# SENSORS_FMU_REV_2A.net
KiCad netlist of a schematic drawn in Altium Designer
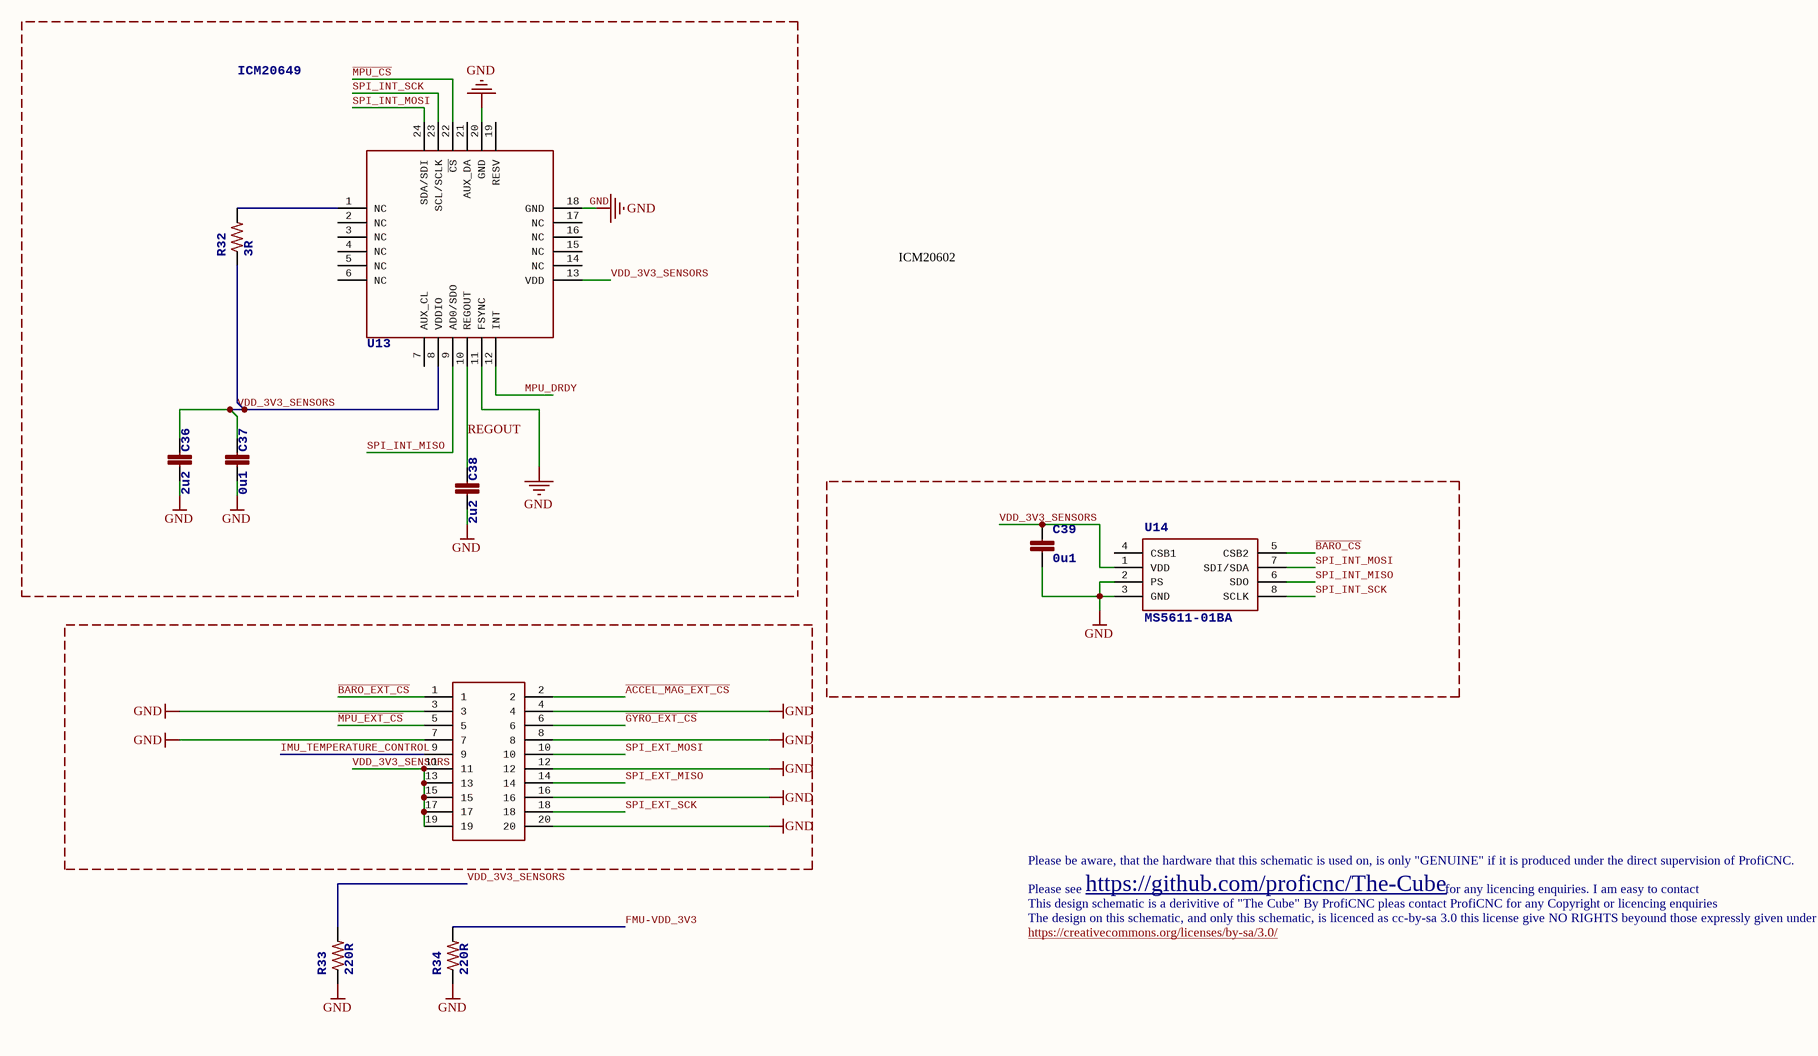
[diagram p0: SENSORS_FMU_REV_2A.SchDoc]

(export (version "E")
  (design (tool "Eeschema 10.0.6"))
  (components
    (comp (ref "C36")
      (value "2u2")
      (footprint "0603-CAP")
      (description "CAP CER 2.2UF 16V 10% X6S 0603")
      (libsource (lib "pixhawk2") (part "CAP0603"))
    )
    (comp (ref "C37")
      (value "0u1")
      (footprint "0402-CAP")
      (description "CAP CER 0.1UF 16V Y5V 0402")
      (libsource (lib "pixhawk2") (part "CAP0402"))
    )
    (comp (ref "C38")
      (value "2u2")
      (footprint "0603-CAP")
      (description "CAP CER 2.2UF 16V 10% X6S 0603")
      (libsource (lib "pixhawk2") (part "CAP0603"))
    )
    (comp (ref "C39")
      (value "0u1")
      (footprint "0402-CAP")
      (description "CAP CER 0.1UF 16V Y5V 0402")
      (libsource (lib "pixhawk2") (part "CAP0402"))
    )
    (comp (ref "R32")
      (value "3R")
      (footprint "0201-RES")
      (description "RES 3OHM 1/16W 1% 0201 SMD")
      (libsource (lib "altium-import") (part "root_1_RESISTOR0402-RES_"))
    )
    (comp (ref "R33")
      (value "220R")
      (footprint "0402-RES")
      (description "RES 220 OHM 1/16W 1% 0402 SMD")
      (libsource (lib "pixhawk2") (part "RESISTOR0402-RES"))
    )
    (comp (ref "R34")
      (value "220R")
      (footprint "0402-RES")
      (description "RES 220 OHM 1/16W 1% 0402 SMD")
      (libsource (lib "pixhawk2") (part "RESISTOR0402-RES"))
    )
    (comp (ref "U$2")
      (value "DF40C-20-DS")
      (footprint "DF-40C-20DS")
      (description "CONN RCPT 20POS 0.4MM SMD GOLD")
      (libsource (lib "pixhawk2") (part "DF40C-20-DS"))
    )
    (comp (ref "U13")
      (value "ICM20649")
      (footprint "ICM20649")
      (libsource (lib "IMU_REV_2A") (part "ICM20649"))
    )
    (comp (ref "U14")
      (value "MS5611-01BA")
      (footprint "MS5611-01BA")
      (description "Board Mount Pressure Sensors")
      (libsource (lib "pixhawk2") (part "MS5611-01BA"))
    )
  )
  (nets
    (net (code "1") (name "/FMU-VDD_3V3") (class "Default")
      (node (ref "R34") (pin "P$2") (pinfunction "2_P$2") (pintype "passive"))
    )
    (net (code "2") (name "/IMU_TEMPERATURE_CONTROL") (class "Default")
      (node (ref "U$2") (pin "9") (pinfunction "9_9") (pintype "passive"))
    )
    (net (code "3") (name "/MPU_DRDY") (class "Default")
      (node (ref "U13") (pin "12") (pinfunction "INT_12") (pintype "passive"))
    )
    (net (code "4") (name "/REGOUT") (class "Default")
      (node (ref "C38") (pin "P$1") (pinfunction "1_P$1") (pintype "passive"))
      (node (ref "U13") (pin "10") (pinfunction "REGOUT_10") (pintype "passive"))
    )
    (net (code "5") (name "/SPI_EXT_MISO") (class "Default")
      (node (ref "U$2") (pin "14") (pinfunction "14_14") (pintype "passive"))
    )
    (net (code "6") (name "/SPI_EXT_MOSI") (class "Default")
      (node (ref "U$2") (pin "10") (pinfunction "10_10") (pintype "passive"))
    )
    (net (code "7") (name "/SPI_EXT_SCK") (class "Default")
      (node (ref "U$2") (pin "18") (pinfunction "18_18") (pintype "passive"))
    )
    (net (code "8") (name "/SPI_INT_MISO") (class "Default")
      (node (ref "U13") (pin "9") (pinfunction "AD0/SDO_9") (pintype "passive"))
      (node (ref "U14") (pin "6") (pinfunction "SDO_6") (pintype "passive"))
    )
    (net (code "9") (name "/SPI_INT_MOSI") (class "Default")
      (node (ref "U13") (pin "24") (pinfunction "SDA/SDI_24") (pintype "passive"))
      (node (ref "U14") (pin "7") (pinfunction "SDI/SDA_7") (pintype "passive"))
    )
    (net (code "10") (name "/SPI_INT_SCK") (class "Default")
      (node (ref "U13") (pin "23") (pinfunction "SCL/SCLK_23") (pintype "passive"))
      (node (ref "U14") (pin "8") (pinfunction "SCLK_8") (pintype "passive"))
    )
    (net (code "11") (name "/VDD_3V3_SENSORS") (class "Default")
      (node (ref "C36") (pin "P$1") (pinfunction "1_P$1") (pintype "passive"))
      (node (ref "C37") (pin "P$1") (pinfunction "1_P$1") (pintype "passive"))
      (node (ref "C39") (pin "P$1") (pinfunction "1_P$1") (pintype "passive"))
      (node (ref "R32") (pin "1") (pinfunction "1_1") (pintype "passive"))
      (node (ref "R33") (pin "P$2") (pinfunction "2_P$2") (pintype "passive"))
      (node (ref "U$2") (pin "11") (pinfunction "11_11") (pintype "passive"))
      (node (ref "U$2") (pin "13") (pinfunction "13_13") (pintype "passive"))
      (node (ref "U$2") (pin "15") (pinfunction "15_15") (pintype "passive"))
      (node (ref "U$2") (pin "17") (pinfunction "17_17") (pintype "passive"))
      (node (ref "U$2") (pin "19") (pinfunction "19_19") (pintype "passive"))
      (node (ref "U13") (pin "13") (pinfunction "VDD_13") (pintype "passive"))
      (node (ref "U13") (pin "8") (pinfunction "VDDIO_8") (pintype "passive"))
      (node (ref "U14") (pin "1") (pinfunction "VDD_1") (pintype "passive"))
    )
    (net (code "12") (name "/~{ACCEL_MAG_EXT_CS}") (class "Default")
      (node (ref "U$2") (pin "2") (pinfunction "2_2") (pintype "passive"))
    )
    (net (code "13") (name "/~{BARO_CS}") (class "Default")
      (node (ref "U14") (pin "5") (pinfunction "CSB2_5") (pintype "passive"))
    )
    (net (code "14") (name "/~{BARO_EXT_CS}") (class "Default")
      (node (ref "U$2") (pin "1") (pinfunction "1_1") (pintype "passive"))
    )
    (net (code "15") (name "/~{GYRO_EXT_CS}") (class "Default")
      (node (ref "U$2") (pin "6") (pinfunction "6_6") (pintype "passive"))
    )
    (net (code "16") (name "/~{MPU_CS}") (class "Default")
      (node (ref "U13") (pin "22") (pinfunction "~{CS}_22") (pintype "passive"))
    )
    (net (code "17") (name "/~{MPU_EXT_CS}") (class "Default")
      (node (ref "U$2") (pin "5") (pinfunction "5_5") (pintype "passive"))
    )
    (net (code "18") (name "GND") (class "Default")
      (node (ref "C36") (pin "P$2") (pinfunction "2_P$2") (pintype "passive"))
      (node (ref "C37") (pin "P$2") (pinfunction "2_P$2") (pintype "passive"))
      (node (ref "C38") (pin "P$2") (pinfunction "2_P$2") (pintype "passive"))
      (node (ref "C39") (pin "P$2") (pinfunction "2_P$2") (pintype "passive"))
      (node (ref "R33") (pin "P$1") (pinfunction "1_P$1") (pintype "passive"))
      (node (ref "R34") (pin "P$1") (pinfunction "1_P$1") (pintype "passive"))
      (node (ref "U$2") (pin "12") (pinfunction "12_12") (pintype "passive"))
      (node (ref "U$2") (pin "16") (pinfunction "16_16") (pintype "passive"))
      (node (ref "U$2") (pin "20") (pinfunction "20_20") (pintype "passive"))
      (node (ref "U$2") (pin "3") (pinfunction "3_3") (pintype "passive"))
      (node (ref "U$2") (pin "4") (pinfunction "4_4") (pintype "passive"))
      (node (ref "U$2") (pin "7") (pinfunction "7_7") (pintype "passive"))
      (node (ref "U$2") (pin "8") (pinfunction "8_8") (pintype "passive"))
      (node (ref "U13") (pin "11") (pinfunction "FSYNC_11") (pintype "passive"))
      (node (ref "U13") (pin "18") (pinfunction "GND_18") (pintype "passive"))
      (node (ref "U13") (pin "20") (pinfunction "GND_20") (pintype "passive"))
      (node (ref "U14") (pin "2") (pinfunction "PS_2") (pintype "passive"))
      (node (ref "U14") (pin "3") (pinfunction "GND_3") (pintype "passive"))
    )
    (net (code "19") (name "Net-(R32-Pad2)") (class "Default")
      (node (ref "R32") (pin "2") (pinfunction "2_2") (pintype "passive"))
      (node (ref "U13") (pin "1") (pinfunction "NC_1") (pintype "passive"))
    )
    (net (code "20") (name "unconnected-(U13-AUX_CL-Pad7)") (class "Default")
      (node (ref "U13") (pin "7") (pinfunction "AUX_CL_7") (pintype "passive"))
    )
    (net (code "21") (name "unconnected-(U13-AUX_DA-Pad21)") (class "Default")
      (node (ref "U13") (pin "21") (pinfunction "AUX_DA_21") (pintype "passive"))
    )
    (net (code "22") (name "unconnected-(U13-NC-Pad2)") (class "Default")
      (node (ref "U13") (pin "2") (pinfunction "NC_2") (pintype "passive"))
    )
    (net (code "23") (name "unconnected-(U13-NC-Pad3)") (class "Default")
      (node (ref "U13") (pin "3") (pinfunction "NC_3") (pintype "passive"))
    )
    (net (code "24") (name "unconnected-(U13-NC-Pad4)") (class "Default")
      (node (ref "U13") (pin "4") (pinfunction "NC_4") (pintype "passive"))
    )
    (net (code "25") (name "unconnected-(U13-NC-Pad5)") (class "Default")
      (node (ref "U13") (pin "5") (pinfunction "NC_5") (pintype "passive"))
    )
    (net (code "26") (name "unconnected-(U13-NC-Pad6)") (class "Default")
      (node (ref "U13") (pin "6") (pinfunction "NC_6") (pintype "passive"))
    )
    (net (code "27") (name "unconnected-(U13-NC-Pad14)") (class "Default")
      (node (ref "U13") (pin "14") (pinfunction "NC_14") (pintype "passive"))
    )
    (net (code "28") (name "unconnected-(U13-NC-Pad15)") (class "Default")
      (node (ref "U13") (pin "15") (pinfunction "NC_15") (pintype "passive"))
    )
    (net (code "29") (name "unconnected-(U13-NC-Pad16)") (class "Default")
      (node (ref "U13") (pin "16") (pinfunction "NC_16") (pintype "passive"))
    )
    (net (code "30") (name "unconnected-(U13-NC-Pad17)") (class "Default")
      (node (ref "U13") (pin "17") (pinfunction "NC_17") (pintype "passive"))
    )
    (net (code "31") (name "unconnected-(U13-RESV-Pad19)") (class "Default")
      (node (ref "U13") (pin "19") (pinfunction "RESV_19") (pintype "passive"))
    )
    (net (code "32") (name "unconnected-(U14-CSB1-Pad4)") (class "Default")
      (node (ref "U14") (pin "4") (pinfunction "CSB1_4") (pintype "passive"))
    )
  )
)
